# Photomodule.net
KiCad netlist of a schematic drawn in Altium Designer
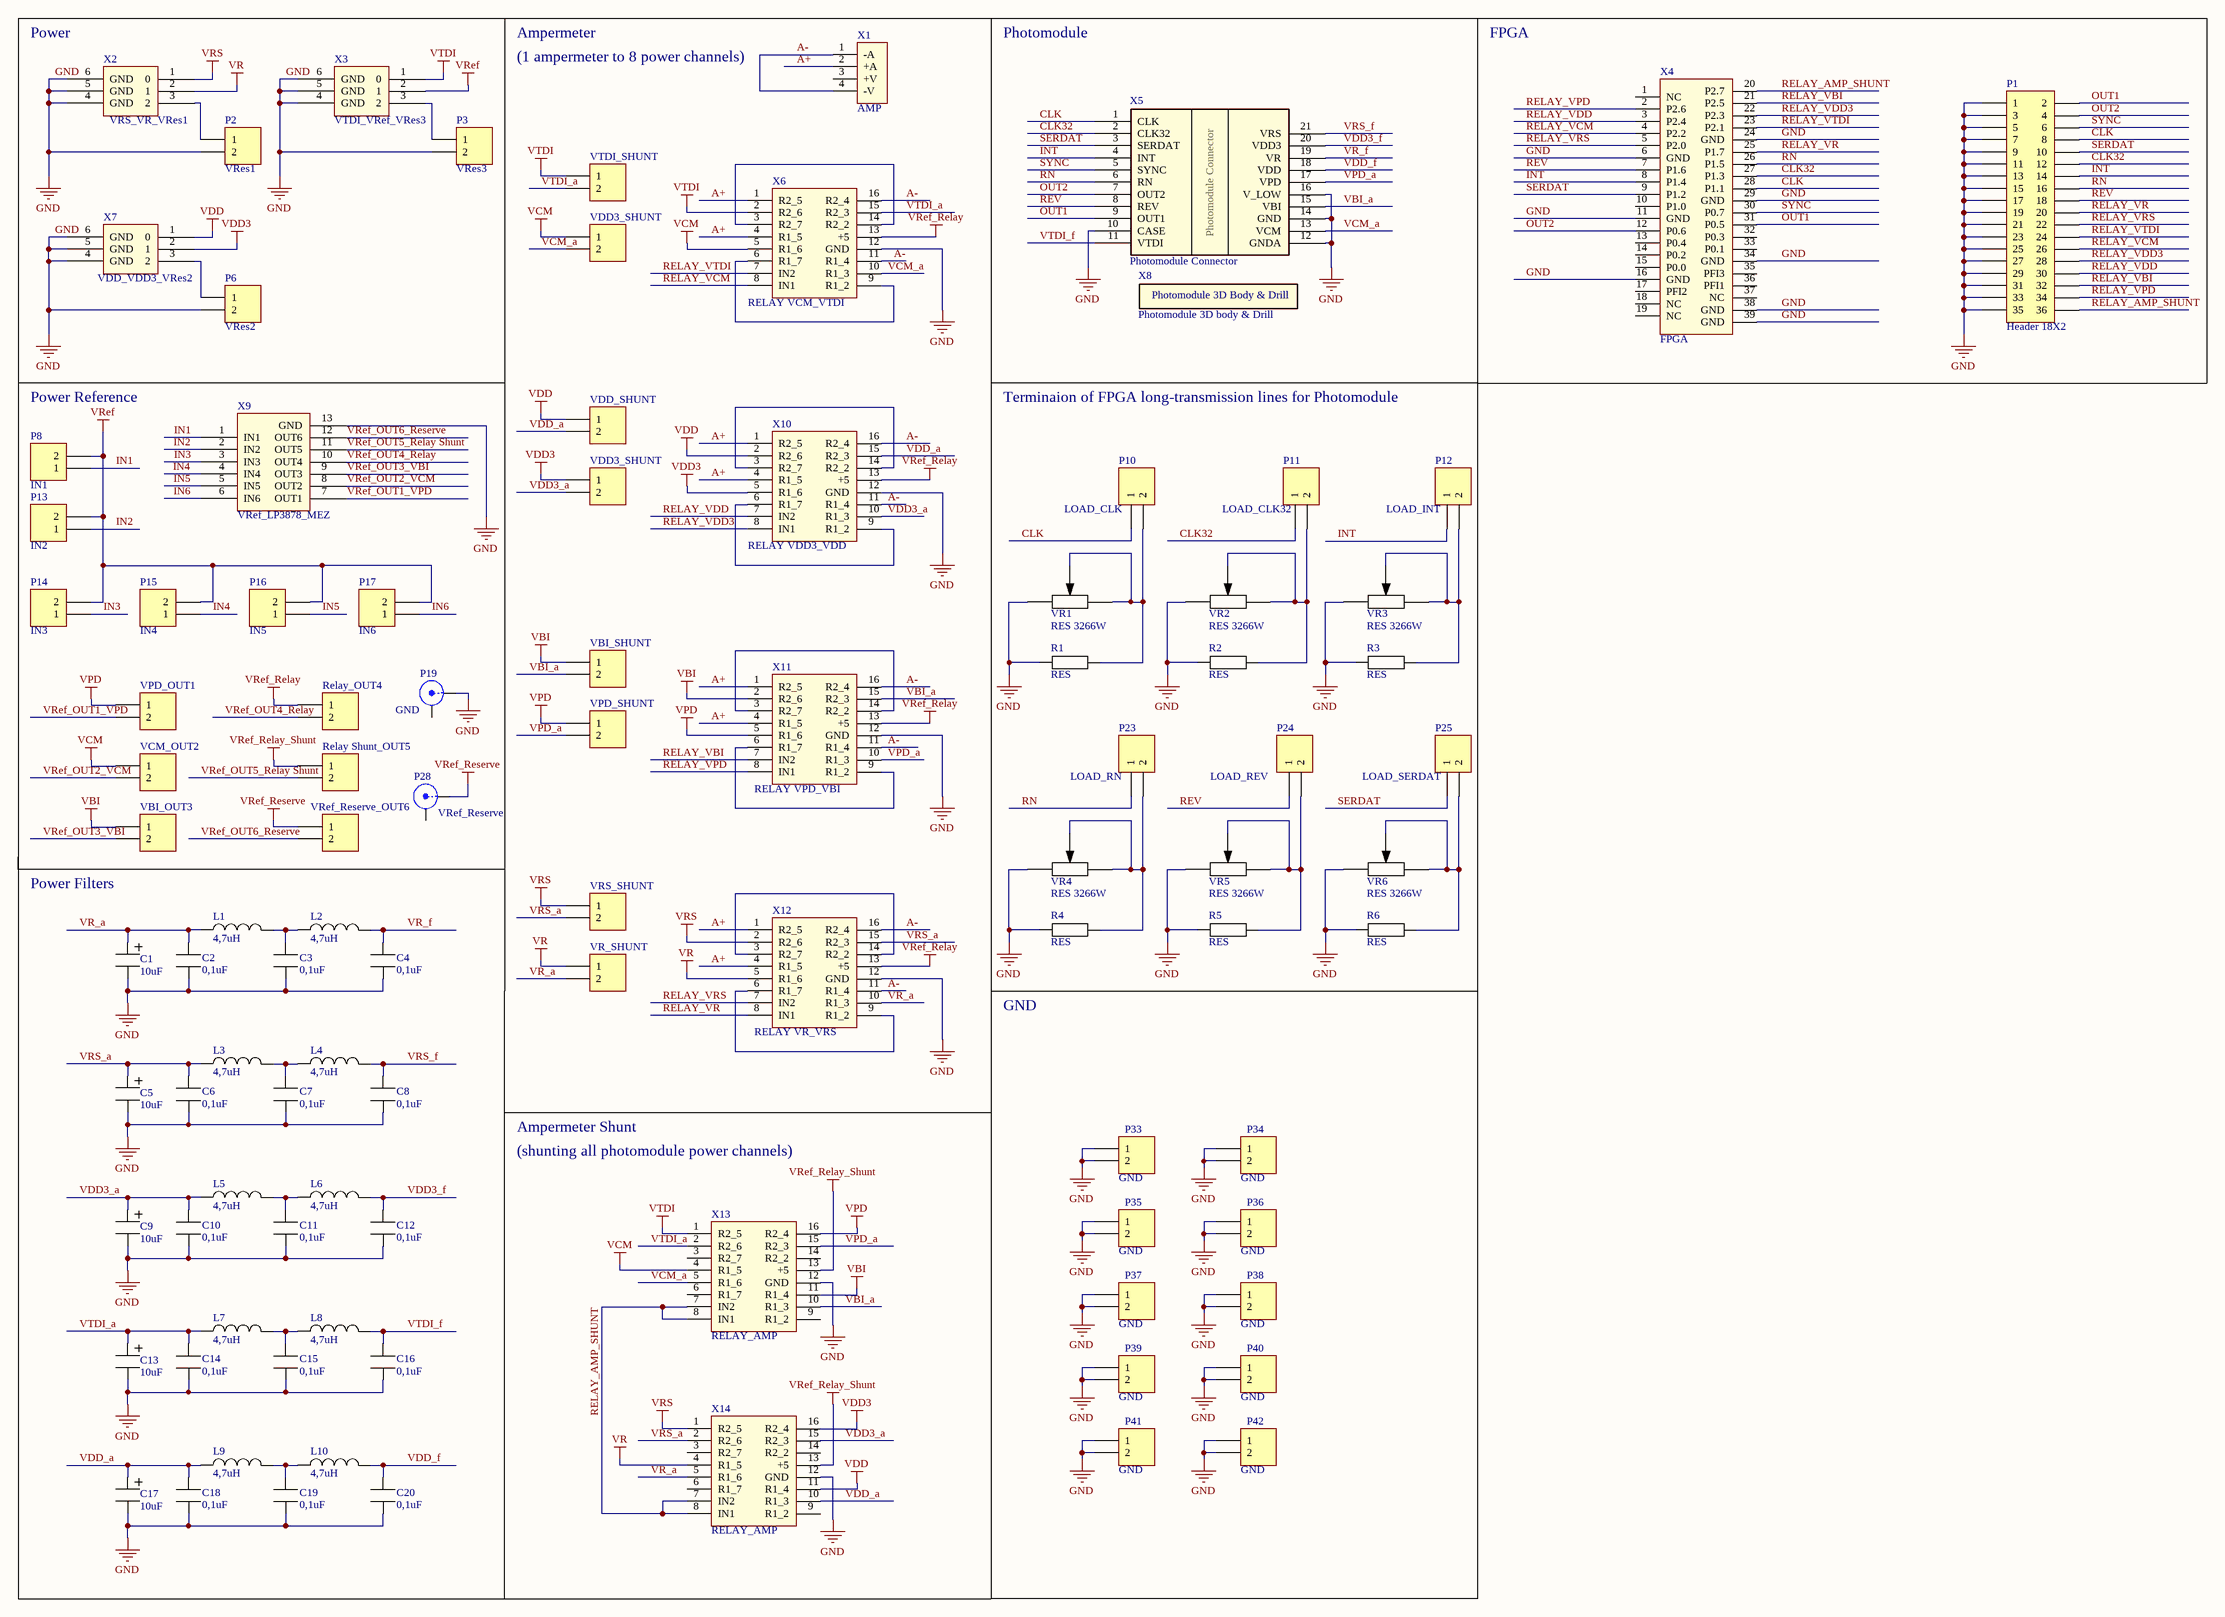
[diagram p0: Photomodule.SchDoc]

(export (version "E")
  (design (tool "Eeschema 10.0.6"))
  (components
    (comp (ref "C1")
      (value "10uF")
      (footprint "aab_Passive:CAP_TANT_TypeC")
      (libsource (lib "aab_Schlib") (part "CAP_Tantalum"))
    )
    (comp (ref "C2")
      (value "0,1uF")
      (footprint "aab_Passive:CAP_0603")
      (libsource (lib "aab_Schlib") (part "CAP"))
    )
    (comp (ref "C3")
      (value "0,1uF")
      (footprint "aab_Passive:CAP_0603")
      (libsource (lib "aab_Schlib") (part "CAP"))
    )
    (comp (ref "C4")
      (value "0,1uF")
      (footprint "aab_Passive:CAP_0603")
      (libsource (lib "aab_Schlib") (part "CAP"))
    )
    (comp (ref "C5")
      (value "10uF")
      (footprint "aab_Passive:CAP_TANT_TypeC")
      (libsource (lib "aab_Schlib") (part "CAP_Tantalum"))
    )
    (comp (ref "C6")
      (value "0,1uF")
      (footprint "aab_Passive:CAP_0603")
      (libsource (lib "aab_Schlib") (part "CAP"))
    )
    (comp (ref "C7")
      (value "0,1uF")
      (footprint "aab_Passive:CAP_0603")
      (libsource (lib "aab_Schlib") (part "CAP"))
    )
    (comp (ref "C8")
      (value "0,1uF")
      (footprint "aab_Passive:CAP_0603")
      (libsource (lib "aab_Schlib") (part "CAP"))
    )
    (comp (ref "C9")
      (value "10uF")
      (footprint "aab_Passive:CAP_TANT_TypeC")
      (libsource (lib "aab_Schlib") (part "CAP_Tantalum"))
    )
    (comp (ref "C10")
      (value "0,1uF")
      (footprint "aab_Passive:CAP_0603")
      (libsource (lib "aab_Schlib") (part "CAP"))
    )
    (comp (ref "C11")
      (value "0,1uF")
      (footprint "aab_Passive:CAP_0603")
      (libsource (lib "aab_Schlib") (part "CAP"))
    )
    (comp (ref "C12")
      (value "0,1uF")
      (footprint "aab_Passive:CAP_0603")
      (libsource (lib "aab_Schlib") (part "CAP"))
    )
    (comp (ref "C13")
      (value "10uF")
      (footprint "aab_Passive:CAP_TANT_TypeC")
      (libsource (lib "aab_Schlib") (part "CAP_Tantalum"))
    )
    (comp (ref "C14")
      (value "0,1uF")
      (footprint "aab_Passive:CAP_0603")
      (libsource (lib "aab_Schlib") (part "CAP"))
    )
    (comp (ref "C15")
      (value "0,1uF")
      (footprint "aab_Passive:CAP_0603")
      (libsource (lib "aab_Schlib") (part "CAP"))
    )
    (comp (ref "C16")
      (value "0,1uF")
      (footprint "aab_Passive:CAP_0603")
      (libsource (lib "aab_Schlib") (part "CAP"))
    )
    (comp (ref "C17")
      (value "10uF")
      (footprint "aab_Passive:CAP_TANT_TypeC")
      (libsource (lib "aab_Schlib") (part "CAP_Tantalum"))
    )
    (comp (ref "C18")
      (value "0,1uF")
      (footprint "aab_Passive:CAP_0603")
      (libsource (lib "aab_Schlib") (part "CAP"))
    )
    (comp (ref "C19")
      (value "0,1uF")
      (footprint "aab_Passive:CAP_0603")
      (libsource (lib "aab_Schlib") (part "CAP"))
    )
    (comp (ref "C20")
      (value "0,1uF")
      (footprint "aab_Passive:CAP_0603")
      (libsource (lib "aab_Schlib") (part "CAP"))
    )
    (comp (ref "L1")
      (value "4,7uH")
      (footprint "aab_Passive:IND_2520")
      (libsource (lib "aab_Schlib") (part "IND"))
    )
    (comp (ref "L2")
      (value "4,7uH")
      (footprint "aab_Passive:IND_2520")
      (libsource (lib "aab_Schlib") (part "IND"))
    )
    (comp (ref "L3")
      (value "4,7uH")
      (footprint "aab_Passive:IND_2520")
      (libsource (lib "aab_Schlib") (part "IND"))
    )
    (comp (ref "L4")
      (value "4,7uH")
      (footprint "aab_Passive:IND_2520")
      (libsource (lib "aab_Schlib") (part "IND"))
    )
    (comp (ref "L5")
      (value "4,7uH")
      (footprint "aab_Passive:IND_2520")
      (libsource (lib "aab_Schlib") (part "IND"))
    )
    (comp (ref "L6")
      (value "4,7uH")
      (footprint "aab_Passive:IND_2520")
      (libsource (lib "aab_Schlib") (part "IND"))
    )
    (comp (ref "L7")
      (value "4,7uH")
      (footprint "aab_Passive:IND_2520")
      (libsource (lib "aab_Schlib") (part "IND"))
    )
    (comp (ref "L8")
      (value "4,7uH")
      (footprint "aab_Passive:IND_2520")
      (libsource (lib "aab_Schlib") (part "IND"))
    )
    (comp (ref "L9")
      (value "4,7uH")
      (footprint "aab_Passive:IND_2520")
      (libsource (lib "aab_Schlib") (part "IND"))
    )
    (comp (ref "L10")
      (value "4,7uH")
      (footprint "aab_Passive:IND_2520")
      (libsource (lib "aab_Schlib") (part "IND"))
    )
    (comp (ref "P1")
      (value "Header 18X2")
      (footprint "HDR2X18")
      (description "Header, 18-Pin, Dual row")
      (fields (field (name "PUBLISHER") "Altium Limited"))
      (libsource (lib "Miscellaneous Connectors") (part "Header 18X2"))
    )
    (comp (ref "P2")
      (value "VRes1")
      (footprint "HDR1X2")
      (description "Header, 2-Pin")
      (fields (field (name "PUBLISHER") "Altium Limited"))
      (libsource (lib "Miscellaneous Connectors") (part "Header 2"))
    )
    (comp (ref "P3")
      (value "VRes3")
      (footprint "HDR1X2")
      (description "Header, 2-Pin")
      (fields (field (name "PUBLISHER") "Altium Limited"))
      (libsource (lib "Miscellaneous Connectors") (part "Header 2"))
    )
    (comp (ref "P4")
      (value "VTDI_SHUNT")
      (footprint "HDR1X2")
      (description "Header, 2-Pin")
      (fields (field (name "PUBLISHER") "Altium Limited"))
      (libsource (lib "Miscellaneous Connectors") (part "Header 2"))
    )
    (comp (ref "P5")
      (value "VDD3_SHUNT")
      (footprint "HDR1X2")
      (description "Header, 2-Pin")
      (fields (field (name "PUBLISHER") "Altium Limited"))
      (libsource (lib "Miscellaneous Connectors") (part "Header 2"))
    )
    (comp (ref "P6")
      (value "VRes2")
      (footprint "HDR1X2")
      (description "Header, 2-Pin")
      (fields (field (name "PUBLISHER") "Altium Limited"))
      (libsource (lib "Miscellaneous Connectors") (part "Header 2"))
    )
    (comp (ref "P7")
      (value "VDD_SHUNT")
      (footprint "HDR1X2")
      (description "Header, 2-Pin")
      (fields (field (name "PUBLISHER") "Altium Limited"))
      (libsource (lib "Miscellaneous Connectors") (part "Header 2"))
    )
    (comp (ref "P8")
      (value "IN1")
      (footprint "HDR1X2")
      (description "Header, 2-Pin")
      (fields (field (name "PUBLISHER") "Altium Limited"))
      (libsource (lib "") (part "Header 2_1"))
    )
    (comp (ref "P9")
      (value "VDD3_SHUNT")
      (footprint "HDR1X2")
      (description "Header, 2-Pin")
      (fields (field (name "PUBLISHER") "Altium Limited"))
      (libsource (lib "Miscellaneous Connectors") (part "Header 2"))
    )
    (comp (ref "P10")
      (value "LOAD_CLK")
      (footprint "HDR1X2")
      (description "Header, 2-Pin")
      (fields (field (name "PUBLISHER") "Altium Limited"))
      (libsource (lib "") (part "Header 2_2"))
    )
    (comp (ref "P11")
      (value "LOAD_CLK32")
      (footprint "HDR1X2")
      (description "Header, 2-Pin")
      (fields (field (name "PUBLISHER") "Altium Limited"))
      (libsource (lib "") (part "Header 2_2"))
    )
    (comp (ref "P12")
      (value "LOAD_INT")
      (footprint "HDR1X2")
      (description "Header, 2-Pin")
      (fields (field (name "PUBLISHER") "Altium Limited"))
      (libsource (lib "") (part "Header 2_2"))
    )
    (comp (ref "P13")
      (value "IN2")
      (footprint "HDR1X2")
      (description "Header, 2-Pin")
      (fields (field (name "PUBLISHER") "Altium Limited"))
      (libsource (lib "") (part "Header 2_1"))
    )
    (comp (ref "P14")
      (value "IN3")
      (footprint "HDR1X2")
      (description "Header, 2-Pin")
      (fields (field (name "PUBLISHER") "Altium Limited"))
      (libsource (lib "") (part "Header 2_1"))
    )
    (comp (ref "P15")
      (value "IN4")
      (footprint "HDR1X2")
      (description "Header, 2-Pin")
      (fields (field (name "PUBLISHER") "Altium Limited"))
      (libsource (lib "") (part "Header 2_1"))
    )
    (comp (ref "P16")
      (value "IN5")
      (footprint "HDR1X2")
      (description "Header, 2-Pin")
      (fields (field (name "PUBLISHER") "Altium Limited"))
      (libsource (lib "") (part "Header 2_1"))
    )
    (comp (ref "P17")
      (value "IN6")
      (footprint "HDR1X2")
      (description "Header, 2-Pin")
      (fields (field (name "PUBLISHER") "Altium Limited"))
      (libsource (lib "") (part "Header 2_1"))
    )
    (comp (ref "P18")
      (value "VBI_SHUNT")
      (footprint "HDR1X2")
      (description "Header, 2-Pin")
      (fields (field (name "PUBLISHER") "Altium Limited"))
      (libsource (lib "Miscellaneous Connectors") (part "Header 2"))
    )
    (comp (ref "P19")
      (value "GND")
      (footprint "BNC_RA CON")
      (description "BNC Elbow Connector")
      (fields (field (name "PUBLISHER") "Altium Limited"))
      (libsource (lib "Miscellaneous Connectors") (part "BNC"))
    )
    (comp (ref "P20")
      (value "VPD_OUT1")
      (footprint "HDR1X2")
      (description "Header, 2-Pin")
      (fields (field (name "PUBLISHER") "Altium Limited"))
      (libsource (lib "Miscellaneous Connectors") (part "Header 2"))
    )
    (comp (ref "P21")
      (value "Relay_OUT4")
      (footprint "HDR1X2")
      (description "Header, 2-Pin")
      (fields (field (name "PUBLISHER") "Altium Limited"))
      (libsource (lib "Miscellaneous Connectors") (part "Header 2"))
    )
    (comp (ref "P22")
      (value "VPD_SHUNT")
      (footprint "HDR1X2")
      (description "Header, 2-Pin")
      (fields (field (name "PUBLISHER") "Altium Limited"))
      (libsource (lib "Miscellaneous Connectors") (part "Header 2"))
    )
    (comp (ref "P23")
      (value "LOAD_RN")
      (footprint "HDR1X2")
      (description "Header, 2-Pin")
      (fields (field (name "PUBLISHER") "Altium Limited"))
      (libsource (lib "") (part "Header 2_2"))
    )
    (comp (ref "P24")
      (value "LOAD_REV")
      (footprint "HDR1X2")
      (description "Header, 2-Pin")
      (fields (field (name "PUBLISHER") "Altium Limited"))
      (libsource (lib "") (part "Header 2_2"))
    )
    (comp (ref "P25")
      (value "LOAD_SERDAT")
      (footprint "HDR1X2")
      (description "Header, 2-Pin")
      (fields (field (name "PUBLISHER") "Altium Limited"))
      (libsource (lib "") (part "Header 2_2"))
    )
    (comp (ref "P26")
      (value "VCM_OUT2")
      (footprint "HDR1X2")
      (description "Header, 2-Pin")
      (fields (field (name "PUBLISHER") "Altium Limited"))
      (libsource (lib "Miscellaneous Connectors") (part "Header 2"))
    )
    (comp (ref "P27")
      (value "Relay Shunt_OUT5")
      (footprint "HDR1X2")
      (description "Header, 2-Pin")
      (fields (field (name "PUBLISHER") "Altium Limited"))
      (libsource (lib "Miscellaneous Connectors") (part "Header 2"))
    )
    (comp (ref "P28")
      (value "VRef_Reserve")
      (footprint "BNC_RA CON")
      (description "BNC Elbow Connector")
      (fields (field (name "PUBLISHER") "Altium Limited"))
      (libsource (lib "Miscellaneous Connectors") (part "BNC"))
    )
    (comp (ref "P29")
      (value "VBI_OUT3")
      (footprint "HDR1X2")
      (description "Header, 2-Pin")
      (fields (field (name "PUBLISHER") "Altium Limited"))
      (libsource (lib "Miscellaneous Connectors") (part "Header 2"))
    )
    (comp (ref "P30")
      (value "VRef_Reserve_OUT6")
      (footprint "HDR1X2")
      (description "Header, 2-Pin")
      (fields (field (name "PUBLISHER") "Altium Limited"))
      (libsource (lib "Miscellaneous Connectors") (part "Header 2"))
    )
    (comp (ref "P31")
      (value "VRS_SHUNT")
      (footprint "HDR1X2")
      (description "Header, 2-Pin")
      (fields (field (name "PUBLISHER") "Altium Limited"))
      (libsource (lib "Miscellaneous Connectors") (part "Header 2"))
    )
    (comp (ref "P32")
      (value "VR_SHUNT")
      (footprint "HDR1X2")
      (description "Header, 2-Pin")
      (fields (field (name "PUBLISHER") "Altium Limited"))
      (libsource (lib "Miscellaneous Connectors") (part "Header 2"))
    )
    (comp (ref "P33")
      (value "GND")
      (footprint "HDR1X2")
      (description "Header, 2-Pin")
      (fields (field (name "PUBLISHER") "Altium Limited"))
      (libsource (lib "Miscellaneous Connectors") (part "Header 2"))
    )
    (comp (ref "P34")
      (value "GND")
      (footprint "HDR1X2")
      (description "Header, 2-Pin")
      (fields (field (name "PUBLISHER") "Altium Limited"))
      (libsource (lib "Miscellaneous Connectors") (part "Header 2"))
    )
    (comp (ref "P35")
      (value "GND")
      (footprint "HDR1X2")
      (description "Header, 2-Pin")
      (fields (field (name "PUBLISHER") "Altium Limited"))
      (libsource (lib "Miscellaneous Connectors") (part "Header 2"))
    )
    (comp (ref "P36")
      (value "GND")
      (footprint "HDR1X2")
      (description "Header, 2-Pin")
      (fields (field (name "PUBLISHER") "Altium Limited"))
      (libsource (lib "Miscellaneous Connectors") (part "Header 2"))
    )
    (comp (ref "P37")
      (value "GND")
      (footprint "HDR1X2")
      (description "Header, 2-Pin")
      (fields (field (name "PUBLISHER") "Altium Limited"))
      (libsource (lib "Miscellaneous Connectors") (part "Header 2"))
    )
    (comp (ref "P38")
      (value "GND")
      (footprint "HDR1X2")
      (description "Header, 2-Pin")
      (fields (field (name "PUBLISHER") "Altium Limited"))
      (libsource (lib "Miscellaneous Connectors") (part "Header 2"))
    )
    (comp (ref "P39")
      (value "GND")
      (footprint "HDR1X2")
      (description "Header, 2-Pin")
      (fields (field (name "PUBLISHER") "Altium Limited"))
      (libsource (lib "Miscellaneous Connectors") (part "Header 2"))
    )
    (comp (ref "P40")
      (value "GND")
      (footprint "HDR1X2")
      (description "Header, 2-Pin")
      (fields (field (name "PUBLISHER") "Altium Limited"))
      (libsource (lib "Miscellaneous Connectors") (part "Header 2"))
    )
    (comp (ref "P41")
      (value "GND")
      (footprint "HDR1X2")
      (description "Header, 2-Pin")
      (fields (field (name "PUBLISHER") "Altium Limited"))
      (libsource (lib "Miscellaneous Connectors") (part "Header 2"))
    )
    (comp (ref "P42")
      (value "GND")
      (footprint "HDR1X2")
      (description "Header, 2-Pin")
      (fields (field (name "PUBLISHER") "Altium Limited"))
      (libsource (lib "Miscellaneous Connectors") (part "Header 2"))
    )
    (comp (ref "R1")
      (value "RES")
      (footprint "aab_Passive:RES_0805")
      (libsource (lib "aab_Schlib") (part "RES"))
    )
    (comp (ref "R2")
      (value "RES")
      (footprint "aab_Passive:RES_0805")
      (libsource (lib "aab_Schlib") (part "RES"))
    )
    (comp (ref "R3")
      (value "RES")
      (footprint "aab_Passive:RES_0805")
      (libsource (lib "aab_Schlib") (part "RES"))
    )
    (comp (ref "R4")
      (value "RES")
      (footprint "aab_Passive:RES_0805")
      (libsource (lib "aab_Schlib") (part "RES"))
    )
    (comp (ref "R5")
      (value "RES")
      (footprint "aab_Passive:RES_0805")
      (libsource (lib "aab_Schlib") (part "RES"))
    )
    (comp (ref "R6")
      (value "RES")
      (footprint "aab_Passive:RES_0805")
      (libsource (lib "aab_Schlib") (part "RES"))
    )
    (comp (ref "VR1")
      (value "RES 3266W")
      (footprint "aab_Passive:RES 3266W")
      (libsource (lib "aab_Schlib") (part "RES 3266W"))
    )
    (comp (ref "VR2")
      (value "RES 3266W")
      (footprint "aab_Passive:RES 3266W")
      (libsource (lib "aab_Schlib") (part "RES 3266W"))
    )
    (comp (ref "VR3")
      (value "RES 3266W")
      (footprint "aab_Passive:RES 3266W")
      (libsource (lib "aab_Schlib") (part "RES 3266W"))
    )
    (comp (ref "VR4")
      (value "RES 3266W")
      (footprint "aab_Passive:RES 3266W")
      (libsource (lib "aab_Schlib") (part "RES 3266W"))
    )
    (comp (ref "VR5")
      (value "RES 3266W")
      (footprint "aab_Passive:RES 3266W")
      (libsource (lib "aab_Schlib") (part "RES 3266W"))
    )
    (comp (ref "VR6")
      (value "RES 3266W")
      (footprint "aab_Passive:RES 3266W")
      (libsource (lib "aab_Schlib") (part "RES 3266W"))
    )
    (comp (ref "X1")
      (value "AMP")
      (footprint "AMP_VOLTMETR")
      (libsource (lib "msp_SchLib") (part "AMP_VOLTMETR"))
    )
    (comp (ref "X2")
      (value "VRS_VR_VRes1")
      (footprint "vpl_Passive_NEW:POWER")
      (libsource (lib "vpl_Schlib_NEW") (part "POWER"))
    )
    (comp (ref "X3")
      (value "VTDI_VRef_VRes3")
      (footprint "vpl_Passive_NEW:POWER")
      (libsource (lib "vpl_Schlib_NEW") (part "POWER"))
    )
    (comp (ref "X4")
      (value "FPGA")
      (footprint "CHEAP_CONN_FEMALE")
      (libsource (lib "vpl_Schlib") (part "CHEAP_CON_37_FEMALE"))
    )
    (comp (ref "X5")
      (value "Photomodule Connector")
      (footprint "aab_Active:Photomodule_Electric")
      (libsource (lib "aab_Schlib") (part "Photomodule Connector"))
    )
    (comp (ref "X6")
      (value "RELAY VCM_VTDI")
      (footprint "RELAY_MODULE")
      (libsource (lib "vpl_Schlib") (part "MEZON_RELAY"))
    )
    (comp (ref "X7")
      (value "VDD_VDD3_VRes2")
      (footprint "vpl_Passive_NEW:POWER")
      (libsource (lib "vpl_Schlib_NEW") (part "POWER"))
    )
    (comp (ref "X8")
      (value "Photomodule 3D body & Drill")
      (footprint "aab_Passive:Photomodule_3D Body & Drill")
      (libsource (lib "aab_Schlib") (part "Phoromodule 3D body & Drill"))
    )
    (comp (ref "X9")
      (value "VRef_LP3878_MEZ")
      (footprint "aab_Active:VRef_LP3878_MEZ")
      (libsource (lib "aab_Schlib") (part "VRef_LP3878_MEZ"))
    )
    (comp (ref "X10")
      (value "RELAY VDD3_VDD")
      (footprint "RELAY_MODULE")
      (libsource (lib "vpl_Schlib") (part "MEZON_RELAY"))
    )
    (comp (ref "X11")
      (value "RELAY VPD_VBI")
      (footprint "RELAY_MODULE")
      (libsource (lib "vpl_Schlib") (part "MEZON_RELAY"))
    )
    (comp (ref "X12")
      (value "RELAY VR_VRS")
      (footprint "RELAY_MODULE")
      (libsource (lib "vpl_Schlib") (part "MEZON_RELAY"))
    )
    (comp (ref "X13")
      (value "RELAY_AMP")
      (footprint "RELAY_MODULE")
      (libsource (lib "vpl_Schlib") (part "MEZON_RELAY"))
    )
    (comp (ref "X14")
      (value "RELAY_AMP")
      (footprint "RELAY_MODULE")
      (libsource (lib "vpl_Schlib") (part "MEZON_RELAY"))
    )
  )
  (nets
    (net (code "1") (name "/A+") (class "Default")
      (node (ref "X1") (pin "2") (pinfunction "+A_2") (pintype "passive"))
      (node (ref "X10") (pin "1") (pinfunction "R2_5_1") (pintype "passive"))
      (node (ref "X10") (pin "4") (pinfunction "R1_5_4") (pintype "passive"))
      (node (ref "X11") (pin "1") (pinfunction "R2_5_1") (pintype "passive"))
      (node (ref "X11") (pin "4") (pinfunction "R1_5_4") (pintype "passive"))
      (node (ref "X12") (pin "1") (pinfunction "R2_5_1") (pintype "passive"))
      (node (ref "X12") (pin "4") (pinfunction "R1_5_4") (pintype "passive"))
      (node (ref "X6") (pin "1") (pinfunction "R2_5_1") (pintype "passive"))
      (node (ref "X6") (pin "4") (pinfunction "R1_5_4") (pintype "passive"))
    )
    (net (code "2") (name "/A-") (class "Default")
      (node (ref "X1") (pin "1") (pinfunction "-A_1") (pintype "passive"))
      (node (ref "X1") (pin "4") (pinfunction "-V_4") (pintype "passive"))
      (node (ref "X10") (pin "11") (pinfunction "R1_4_11") (pintype "passive"))
      (node (ref "X10") (pin "16") (pinfunction "R2_4_16") (pintype "passive"))
      (node (ref "X11") (pin "11") (pinfunction "R1_4_11") (pintype "passive"))
      (node (ref "X11") (pin "16") (pinfunction "R2_4_16") (pintype "passive"))
      (node (ref "X12") (pin "11") (pinfunction "R1_4_11") (pintype "passive"))
      (node (ref "X12") (pin "16") (pinfunction "R2_4_16") (pintype "passive"))
      (node (ref "X6") (pin "11") (pinfunction "R1_4_11") (pintype "passive"))
      (node (ref "X6") (pin "16") (pinfunction "R2_4_16") (pintype "passive"))
    )
    (net (code "3") (name "/CLK") (class "Default")
      (node (ref "P1") (pin "8") (pinfunction "8_8") (pintype "passive"))
      (node (ref "P10") (pin "1") (pinfunction "1_1") (pintype "passive"))
      (node (ref "X4") (pin "28") (pinfunction "P1.1_28") (pintype "passive"))
      (node (ref "X5") (pin "1") (pinfunction "CLK_1") (pintype "passive"))
    )
    (net (code "4") (name "/CLK32") (class "Default")
      (node (ref "P1") (pin "12") (pinfunction "12_12") (pintype "passive"))
      (node (ref "P11") (pin "1") (pinfunction "1_1") (pintype "passive"))
      (node (ref "X4") (pin "27") (pinfunction "P1.3_27") (pintype "passive"))
      (node (ref "X5") (pin "2") (pinfunction "CLK32_2") (pintype "passive"))
    )
    (net (code "5") (name "/IN1") (class "Default")
      (node (ref "P8") (pin "1") (pinfunction "1_1") (pintype "passive"))
      (node (ref "X9") (pin "1") (pinfunction "IN1_1") (pintype "passive"))
    )
    (net (code "6") (name "/IN2") (class "Default")
      (node (ref "P13") (pin "1") (pinfunction "1_1") (pintype "passive"))
      (node (ref "X9") (pin "2") (pinfunction "IN2_2") (pintype "passive"))
    )
    (net (code "7") (name "/IN3") (class "Default")
      (node (ref "P14") (pin "1") (pinfunction "1_1") (pintype "passive"))
      (node (ref "X9") (pin "3") (pinfunction "IN3_3") (pintype "passive"))
    )
    (net (code "8") (name "/IN4") (class "Default")
      (node (ref "P15") (pin "1") (pinfunction "1_1") (pintype "passive"))
      (node (ref "X9") (pin "4") (pinfunction "IN4_4") (pintype "passive"))
    )
    (net (code "9") (name "/IN5") (class "Default")
      (node (ref "P16") (pin "1") (pinfunction "1_1") (pintype "passive"))
      (node (ref "X9") (pin "5") (pinfunction "IN5_5") (pintype "passive"))
    )
    (net (code "10") (name "/IN6") (class "Default")
      (node (ref "P17") (pin "1") (pinfunction "1_1") (pintype "passive"))
      (node (ref "X9") (pin "6") (pinfunction "IN6_6") (pintype "passive"))
    )
    (net (code "11") (name "/INT") (class "Default")
      (node (ref "P1") (pin "14") (pinfunction "14_14") (pintype "passive"))
      (node (ref "P12") (pin "1") (pinfunction "1_1") (pintype "passive"))
      (node (ref "X4") (pin "8") (pinfunction "P1.4_8") (pintype "passive"))
      (node (ref "X5") (pin "4") (pinfunction "INT_4") (pintype "passive"))
    )
    (net (code "12") (name "/OUT1") (class "Default")
      (node (ref "P1") (pin "2") (pinfunction "2_2") (pintype "passive"))
      (node (ref "X4") (pin "31") (pinfunction "P0.5_31") (pintype "passive"))
      (node (ref "X5") (pin "9") (pinfunction "OUT1_9") (pintype "passive"))
    )
    (net (code "13") (name "/OUT2") (class "Default")
      (node (ref "P1") (pin "4") (pinfunction "4_4") (pintype "passive"))
      (node (ref "X4") (pin "12") (pinfunction "P0.6_12") (pintype "passive"))
      (node (ref "X5") (pin "7") (pinfunction "OUT2_7") (pintype "passive"))
    )
    (net (code "14") (name "/RELAY_AMP_SHUNT") (class "Default")
      (node (ref "P1") (pin "36") (pinfunction "36_36") (pintype "passive"))
      (node (ref "X13") (pin "7") (pinfunction "IN2_7") (pintype "passive"))
      (node (ref "X13") (pin "8") (pinfunction "IN1_8") (pintype "passive"))
      (node (ref "X14") (pin "7") (pinfunction "IN2_7") (pintype "passive"))
      (node (ref "X14") (pin "8") (pinfunction "IN1_8") (pintype "passive"))
      (node (ref "X4") (pin "20") (pinfunction "P2.7_20") (pintype "passive"))
    )
    (net (code "15") (name "/RELAY_VBI") (class "Default")
      (node (ref "P1") (pin "32") (pinfunction "32_32") (pintype "passive"))
      (node (ref "X11") (pin "7") (pinfunction "IN2_7") (pintype "passive"))
      (node (ref "X4") (pin "21") (pinfunction "P2.5_21") (pintype "passive"))
    )
    (net (code "16") (name "/RELAY_VCM") (class "Default")
      (node (ref "P1") (pin "26") (pinfunction "26_26") (pintype "passive"))
      (node (ref "X4") (pin "4") (pinfunction "P2.2_4") (pintype "passive"))
      (node (ref "X6") (pin "8") (pinfunction "IN1_8") (pintype "passive"))
    )
    (net (code "17") (name "/RELAY_VDD") (class "Default")
      (node (ref "P1") (pin "30") (pinfunction "30_30") (pintype "passive"))
      (node (ref "X10") (pin "7") (pinfunction "IN2_7") (pintype "passive"))
      (node (ref "X4") (pin "3") (pinfunction "P2.4_3") (pintype "passive"))
    )
    (net (code "18") (name "/RELAY_VDD3") (class "Default")
      (node (ref "P1") (pin "28") (pinfunction "28_28") (pintype "passive"))
      (node (ref "X10") (pin "8") (pinfunction "IN1_8") (pintype "passive"))
      (node (ref "X4") (pin "22") (pinfunction "P2.3_22") (pintype "passive"))
    )
    (net (code "19") (name "/RELAY_VPD") (class "Default")
      (node (ref "P1") (pin "34") (pinfunction "34_34") (pintype "passive"))
      (node (ref "X11") (pin "8") (pinfunction "IN1_8") (pintype "passive"))
      (node (ref "X4") (pin "2") (pinfunction "P2.6_2") (pintype "passive"))
    )
    (net (code "20") (name "/RELAY_VR") (class "Default")
      (node (ref "P1") (pin "20") (pinfunction "20_20") (pintype "passive"))
      (node (ref "X12") (pin "8") (pinfunction "IN1_8") (pintype "passive"))
      (node (ref "X4") (pin "25") (pinfunction "P1.7_25") (pintype "passive"))
    )
    (net (code "21") (name "/RELAY_VRS") (class "Default")
      (node (ref "P1") (pin "22") (pinfunction "22_22") (pintype "passive"))
      (node (ref "X12") (pin "7") (pinfunction "IN2_7") (pintype "passive"))
      (node (ref "X4") (pin "5") (pinfunction "P2.0_5") (pintype "passive"))
    )
    (net (code "22") (name "/RELAY_VTDI") (class "Default")
      (node (ref "P1") (pin "24") (pinfunction "24_24") (pintype "passive"))
      (node (ref "X4") (pin "23") (pinfunction "P2.1_23") (pintype "passive"))
      (node (ref "X6") (pin "7") (pinfunction "IN2_7") (pintype "passive"))
    )
    (net (code "23") (name "/REV") (class "Default")
      (node (ref "P1") (pin "18") (pinfunction "18_18") (pintype "passive"))
      (node (ref "P24") (pin "1") (pinfunction "1_1") (pintype "passive"))
      (node (ref "X4") (pin "7") (pinfunction "P1.6_7") (pintype "passive"))
      (node (ref "X5") (pin "8") (pinfunction "REV_8") (pintype "passive"))
    )
    (net (code "24") (name "/RN") (class "Default")
      (node (ref "P1") (pin "16") (pinfunction "16_16") (pintype "passive"))
      (node (ref "P23") (pin "1") (pinfunction "1_1") (pintype "passive"))
      (node (ref "X4") (pin "26") (pinfunction "P1.5_26") (pintype "passive"))
      (node (ref "X5") (pin "6") (pinfunction "RN_6") (pintype "passive"))
    )
    (net (code "25") (name "/SERDAT") (class "Default")
      (node (ref "P1") (pin "10") (pinfunction "10_10") (pintype "passive"))
      (node (ref "P25") (pin "1") (pinfunction "1_1") (pintype "passive"))
      (node (ref "X4") (pin "9") (pinfunction "P1.2_9") (pintype "passive"))
      (node (ref "X5") (pin "3") (pinfunction "SERDAT_3") (pintype "passive"))
    )
    (net (code "26") (name "/SYNC") (class "Default")
      (node (ref "P1") (pin "6") (pinfunction "6_6") (pintype "passive"))
      (node (ref "X4") (pin "30") (pinfunction "P0.7_30") (pintype "passive"))
      (node (ref "X5") (pin "5") (pinfunction "SYNC_5") (pintype "passive"))
    )
    (net (code "27") (name "/VBI_a") (class "Default")
      (node (ref "P18") (pin "2") (pinfunction "2_2") (pintype "passive"))
      (node (ref "X11") (pin "15") (pinfunction "R2_3_15") (pintype "passive"))
      (node (ref "X13") (pin "10") (pinfunction "R1_3_10") (pintype "passive"))
      (node (ref "X5") (pin "15") (pinfunction "VBI_15") (pintype "passive"))
    )
    (net (code "28") (name "/VCM_a") (class "Default")
      (node (ref "P5") (pin "2") (pinfunction "2_2") (pintype "passive"))
      (node (ref "X13") (pin "5") (pinfunction "R1_6_5") (pintype "passive"))
      (node (ref "X5") (pin "13") (pinfunction "VCM_13") (pintype "passive"))
      (node (ref "X6") (pin "10") (pinfunction "R1_3_10") (pintype "passive"))
    )
    (net (code "29") (name "/VDD3_a") (class "Default")
      (node (ref "C10") (pin "2") (pinfunction "2_2") (pintype "passive"))
      (node (ref "C9") (pin "1") (pinfunction "1_1") (pintype "passive"))
      (node (ref "L5") (pin "1") (pinfunction "1_1") (pintype "passive"))
      (node (ref "P9") (pin "2") (pinfunction "2_2") (pintype "passive"))
      (node (ref "X10") (pin "10") (pinfunction "R1_3_10") (pintype "passive"))
      (node (ref "X14") (pin "15") (pinfunction "R2_3_15") (pintype "passive"))
    )
    (net (code "30") (name "/VDD3_f") (class "Default")
      (node (ref "C12") (pin "2") (pinfunction "2_2") (pintype "passive"))
      (node (ref "L6") (pin "2") (pinfunction "2_2") (pintype "passive"))
      (node (ref "X5") (pin "20") (pinfunction "VDD3_20") (pintype "passive"))
    )
    (net (code "31") (name "/VDD_a") (class "Default")
      (node (ref "C17") (pin "1") (pinfunction "1_1") (pintype "passive"))
      (node (ref "C18") (pin "2") (pinfunction "2_2") (pintype "passive"))
      (node (ref "L9") (pin "1") (pinfunction "1_1") (pintype "passive"))
      (node (ref "P7") (pin "2") (pinfunction "2_2") (pintype "passive"))
      (node (ref "X10") (pin "15") (pinfunction "R2_3_15") (pintype "passive"))
      (node (ref "X14") (pin "10") (pinfunction "R1_3_10") (pintype "passive"))
    )
    (net (code "32") (name "/VDD_f") (class "Default")
      (node (ref "C20") (pin "2") (pinfunction "2_2") (pintype "passive"))
      (node (ref "L10") (pin "2") (pinfunction "2_2") (pintype "passive"))
      (node (ref "X5") (pin "18") (pinfunction "VDD_18") (pintype "passive"))
    )
    (net (code "33") (name "/VPD_a") (class "Default")
      (node (ref "P22") (pin "2") (pinfunction "2_2") (pintype "passive"))
      (node (ref "X11") (pin "10") (pinfunction "R1_3_10") (pintype "passive"))
      (node (ref "X13") (pin "15") (pinfunction "R2_3_15") (pintype "passive"))
      (node (ref "X5") (pin "17") (pinfunction "VPD_17") (pintype "passive"))
    )
    (net (code "34") (name "/VRS_a") (class "Default")
      (node (ref "C5") (pin "1") (pinfunction "1_1") (pintype "passive"))
      (node (ref "C6") (pin "2") (pinfunction "2_2") (pintype "passive"))
      (node (ref "L3") (pin "1") (pinfunction "1_1") (pintype "passive"))
      (node (ref "P31") (pin "2") (pinfunction "2_2") (pintype "passive"))
      (node (ref "X12") (pin "15") (pinfunction "R2_3_15") (pintype "passive"))
      (node (ref "X14") (pin "2") (pinfunction "R2_6_2") (pintype "passive"))
    )
    (net (code "35") (name "/VRS_f") (class "Default")
      (node (ref "C8") (pin "2") (pinfunction "2_2") (pintype "passive"))
      (node (ref "L4") (pin "2") (pinfunction "2_2") (pintype "passive"))
      (node (ref "X5") (pin "21") (pinfunction "VRS_21") (pintype "passive"))
    )
    (net (code "36") (name "/VR_a") (class "Default")
      (node (ref "C1") (pin "1") (pinfunction "1_1") (pintype "passive"))
      (node (ref "C2") (pin "2") (pinfunction "2_2") (pintype "passive"))
      (node (ref "L1") (pin "1") (pinfunction "1_1") (pintype "passive"))
      (node (ref "P32") (pin "2") (pinfunction "2_2") (pintype "passive"))
      (node (ref "X12") (pin "10") (pinfunction "R1_3_10") (pintype "passive"))
      (node (ref "X14") (pin "5") (pinfunction "R1_6_5") (pintype "passive"))
    )
    (net (code "37") (name "/VR_f") (class "Default")
      (node (ref "C4") (pin "2") (pinfunction "2_2") (pintype "passive"))
      (node (ref "L2") (pin "2") (pinfunction "2_2") (pintype "passive"))
      (node (ref "X5") (pin "19") (pinfunction "VR_19") (pintype "passive"))
    )
    (net (code "38") (name "/VRef_OUT1_VPD") (class "Default")
      (node (ref "P20") (pin "2") (pinfunction "2_2") (pintype "passive"))
      (node (ref "X9") (pin "7") (pinfunction "OUT1_7") (pintype "passive"))
    )
    (net (code "39") (name "/VRef_OUT2_VCM") (class "Default")
      (node (ref "P26") (pin "2") (pinfunction "2_2") (pintype "passive"))
      (node (ref "X9") (pin "8") (pinfunction "OUT2_8") (pintype "passive"))
    )
    (net (code "40") (name "/VRef_OUT3_VBI") (class "Default")
      (node (ref "P29") (pin "2") (pinfunction "2_2") (pintype "passive"))
      (node (ref "X9") (pin "9") (pinfunction "OUT3_9") (pintype "passive"))
    )
    (net (code "41") (name "/VRef_OUT4_Relay") (class "Default")
      (node (ref "P21") (pin "2") (pinfunction "2_2") (pintype "passive"))
      (node (ref "X9") (pin "10") (pinfunction "OUT4_10") (pintype "passive"))
    )
    (net (code "42") (name "/VRef_OUT5_Relay Shunt") (class "Default")
      (node (ref "P27") (pin "2") (pinfunction "2_2") (pintype "passive"))
      (node (ref "X9") (pin "11") (pinfunction "OUT5_11") (pintype "passive"))
    )
    (net (code "43") (name "/VRef_OUT6_Reserve") (class "Default")
      (node (ref "P30") (pin "2") (pinfunction "2_2") (pintype "passive"))
      (node (ref "X9") (pin "12") (pinfunction "OUT6_12") (pintype "passive"))
    )
    (net (code "44") (name "/VTDI_a") (class "Default")
      (node (ref "C13") (pin "1") (pinfunction "1_1") (pintype "passive"))
      (node (ref "C14") (pin "2") (pinfunction "2_2") (pintype "passive"))
      (node (ref "L7") (pin "1") (pinfunction "1_1") (pintype "passive"))
      (node (ref "P4") (pin "2") (pinfunction "2_2") (pintype "passive"))
      (node (ref "X13") (pin "2") (pinfunction "R2_6_2") (pintype "passive"))
      (node (ref "X6") (pin "15") (pinfunction "R2_3_15") (pintype "passive"))
    )
    (net (code "45") (name "/VTDI_f") (class "Default")
      (node (ref "C16") (pin "2") (pinfunction "2_2") (pintype "passive"))
      (node (ref "L8") (pin "2") (pinfunction "2_2") (pintype "passive"))
      (node (ref "X5") (pin "11") (pinfunction "VTDI_11") (pintype "passive"))
    )
    (net (code "46") (name "GND") (class "Default")
      (node (ref "C1") (pin "2") (pinfunction "2_2") (pintype "passive"))
      (node (ref "C10") (pin "1") (pinfunction "1_1") (pintype "passive"))
      (node (ref "C11") (pin "1") (pinfunction "1_1") (pintype "passive"))
      (node (ref "C12") (pin "1") (pinfunction "1_1") (pintype "passive"))
      (node (ref "C13") (pin "2") (pinfunction "2_2") (pintype "passive"))
      (node (ref "C14") (pin "1") (pinfunction "1_1") (pintype "passive"))
      (node (ref "C15") (pin "1") (pinfunction "1_1") (pintype "passive"))
      (node (ref "C16") (pin "1") (pinfunction "1_1") (pintype "passive"))
      (node (ref "C17") (pin "2") (pinfunction "2_2") (pintype "passive"))
      (node (ref "C18") (pin "1") (pinfunction "1_1") (pintype "passive"))
      (node (ref "C19") (pin "1") (pinfunction "1_1") (pintype "passive"))
      (node (ref "C2") (pin "1") (pinfunction "1_1") (pintype "passive"))
      (node (ref "C20") (pin "1") (pinfunction "1_1") (pintype "passive"))
      (node (ref "C3") (pin "1") (pinfunction "1_1") (pintype "passive"))
      (node (ref "C4") (pin "1") (pinfunction "1_1") (pintype "passive"))
      (node (ref "C5") (pin "2") (pinfunction "2_2") (pintype "passive"))
      (node (ref "C6") (pin "1") (pinfunction "1_1") (pintype "passive"))
      (node (ref "C7") (pin "1") (pinfunction "1_1") (pintype "passive"))
      (node (ref "C8") (pin "1") (pinfunction "1_1") (pintype "passive"))
      (node (ref "C9") (pin "2") (pinfunction "2_2") (pintype "passive"))
      (node (ref "P1") (pin "1") (pinfunction "1_1") (pintype "passive"))
      (node (ref "P1") (pin "11") (pinfunction "11_11") (pintype "passive"))
      (node (ref "P1") (pin "13") (pinfunction "13_13") (pintype "passive"))
      (node (ref "P1") (pin "15") (pinfunction "15_15") (pintype "passive"))
      (node (ref "P1") (pin "17") (pinfunction "17_17") (pintype "passive"))
      (node (ref "P1") (pin "19") (pinfunction "19_19") (pintype "passive"))
      (node (ref "P1") (pin "21") (pinfunction "21_21") (pintype "passive"))
      (node (ref "P1") (pin "23") (pinfunction "23_23") (pintype "passive"))
      (node (ref "P1") (pin "25") (pinfunction "25_25") (pintype "passive"))
      (node (ref "P1") (pin "27") (pinfunction "27_27") (pintype "passive"))
      (node (ref "P1") (pin "29") (pinfunction "29_29") (pintype "passive"))
      (node (ref "P1") (pin "3") (pinfunction "3_3") (pintype "passive"))
      (node (ref "P1") (pin "31") (pinfunction "31_31") (pintype "passive"))
      (node (ref "P1") (pin "33") (pinfunction "33_33") (pintype "passive"))
      (node (ref "P1") (pin "35") (pinfunction "35_35") (pintype "passive"))
      (node (ref "P1") (pin "5") (pinfunction "5_5") (pintype "passive"))
      (node (ref "P1") (pin "7") (pinfunction "7_7") (pintype "passive"))
      (node (ref "P1") (pin "9") (pinfunction "9_9") (pintype "passive"))
      (node (ref "P19") (pin "1") (pinfunction "X_1") (pintype "passive"))
      (node (ref "P2") (pin "2") (pinfunction "2_2") (pintype "passive"))
      (node (ref "P3") (pin "2") (pinfunction "2_2") (pintype "passive"))
      (node (ref "P33") (pin "1") (pinfunction "1_1") (pintype "passive"))
      (node (ref "P33") (pin "2") (pinfunction "2_2") (pintype "passive"))
      (node (ref "P34") (pin "1") (pinfunction "1_1") (pintype "passive"))
      (node (ref "P34") (pin "2") (pinfunction "2_2") (pintype "passive"))
      (node (ref "P35") (pin "1") (pinfunction "1_1") (pintype "passive"))
      (node (ref "P35") (pin "2") (pinfunction "2_2") (pintype "passive"))
      (node (ref "P36") (pin "1") (pinfunction "1_1") (pintype "passive"))
      (node (ref "P36") (pin "2") (pinfunction "2_2") (pintype "passive"))
      (node (ref "P37") (pin "1") (pinfunction "1_1") (pintype "passive"))
      (node (ref "P37") (pin "2") (pinfunction "2_2") (pintype "passive"))
      (node (ref "P38") (pin "1") (pinfunction "1_1") (pintype "passive"))
      (node (ref "P38") (pin "2") (pinfunction "2_2") (pintype "passive"))
      (node (ref "P39") (pin "1") (pinfunction "1_1") (pintype "passive"))
      (node (ref "P39") (pin "2") (pinfunction "2_2") (pintype "passive"))
      (node (ref "P40") (pin "1") (pinfunction "1_1") (pintype "passive"))
      (node (ref "P40") (pin "2") (pinfunction "2_2") (pintype "passive"))
      (node (ref "P41") (pin "1") (pinfunction "1_1") (pintype "passive"))
      (node (ref "P41") (pin "2") (pinfunction "2_2") (pintype "passive"))
      (node (ref "P42") (pin "1") (pinfunction "1_1") (pintype "passive"))
      (node (ref "P42") (pin "2") (pinfunction "2_2") (pintype "passive"))
      (node (ref "P6") (pin "2") (pinfunction "2_2") (pintype "passive"))
      (node (ref "R1") (pin "1") (pinfunction "1_1") (pintype "passive"))
      (node (ref "R2") (pin "1") (pinfunction "1_1") (pintype "passive"))
      (node (ref "R3") (pin "1") (pinfunction "1_1") (pintype "passive"))
      (node (ref "R4") (pin "1") (pinfunction "1_1") (pintype "passive"))
      (node (ref "R5") (pin "1") (pinfunction "1_1") (pintype "passive"))
      (node (ref "R6") (pin "1") (pinfunction "1_1") (pintype "passive"))
      (node (ref "VR1") (pin "1") (pinfunction "1_1") (pintype "passive"))
      (node (ref "VR2") (pin "1") (pinfunction "1_1") (pintype "passive"))
      (node (ref "VR3") (pin "1") (pinfunction "1_1") (pintype "passive"))
      (node (ref "VR4") (pin "1") (pinfunction "1_1") (pintype "passive"))
      (node (ref "VR5") (pin "1") (pinfunction "1_1") (pintype "passive"))
      (node (ref "VR6") (pin "1") (pinfunction "1_1") (pintype "passive"))
      (node (ref "X10") (pin "12") (pinfunction "GND_12") (pintype "passive"))
      (node (ref "X11") (pin "12") (pinfunction "GND_12") (pintype "passive"))
      (node (ref "X12") (pin "12") (pinfunction "GND_12") (pintype "passive"))
      (node (ref "X13") (pin "12") (pinfunction "GND_12") (pintype "passive"))
      (node (ref "X14") (pin "12") (pinfunction "GND_12") (pintype "passive"))
      (node (ref "X2") (pin "4") (pinfunction "GND_4") (pintype "passive"))
      (node (ref "X2") (pin "5") (pinfunction "GND_5") (pintype "passive"))
      (node (ref "X2") (pin "6") (pinfunction "GND_6") (pintype "passive"))
      (node (ref "X3") (pin "4") (pinfunction "GND_4") (pintype "passive"))
      (node (ref "X3") (pin "5") (pinfunction "GND_5") (pintype "passive"))
      (node (ref "X3") (pin "6") (pinfunction "GND_6") (pintype "passive"))
      (node (ref "X4") (pin "11") (pinfunction "GND_11") (pintype "passive"))
      (node (ref "X4") (pin "16") (pinfunction "GND_16") (pintype "passive"))
      (node (ref "X4") (pin "24") (pinfunction "GND_24") (pintype "passive"))
      (node (ref "X4") (pin "29") (pinfunction "GND_29") (pintype "passive"))
      (node (ref "X4") (pin "34") (pinfunction "GND_34") (pintype "passive"))
      (node (ref "X4") (pin "38") (pinfunction "GND_38") (pintype "passive"))
      (node (ref "X4") (pin "39") (pinfunction "GND_39") (pintype "passive"))
      (node (ref "X4") (pin "6") (pinfunction "GND_6") (pintype "passive"))
      (node (ref "X5") (pin "10") (pinfunction "CASE_10") (pintype "passive"))
      (node (ref "X5") (pin "12") (pinfunction "GNDA_12") (pintype "passive"))
      (node (ref "X5") (pin "14") (pinfunction "GND_14") (pintype "passive"))
      (node (ref "X5") (pin "16") (pinfunction "V_LOW_16") (pintype "passive"))
      (node (ref "X6") (pin "12") (pinfunction "GND_12") (pintype "passive"))
      (node (ref "X7") (pin "4") (pinfunction "GND_4") (pintype "passive"))
      (node (ref "X7") (pin "5") (pinfunction "GND_5") (pintype "passive"))
      (node (ref "X7") (pin "6") (pinfunction "GND_6") (pintype "passive"))
      (node (ref "X9") (pin "13") (pinfunction "GND_13") (pintype "passive"))
    )
    (net (code "47") (name "Net-(C3-Pad2)") (class "Default")
      (node (ref "C3") (pin "2") (pinfunction "2_2") (pintype "passive"))
      (node (ref "L1") (pin "2") (pinfunction "2_2") (pintype "passive"))
      (node (ref "L2") (pin "1") (pinfunction "1_1") (pintype "passive"))
    )
    (net (code "48") (name "Net-(C7-Pad2)") (class "Default")
      (node (ref "C7") (pin "2") (pinfunction "2_2") (pintype "passive"))
      (node (ref "L3") (pin "2") (pinfunction "2_2") (pintype "passive"))
      (node (ref "L4") (pin "1") (pinfunction "1_1") (pintype "passive"))
    )
    (net (code "49") (name "Net-(C11-Pad2)") (class "Default")
      (node (ref "C11") (pin "2") (pinfunction "2_2") (pintype "passive"))
      (node (ref "L5") (pin "2") (pinfunction "2_2") (pintype "passive"))
      (node (ref "L6") (pin "1") (pinfunction "1_1") (pintype "passive"))
    )
    (net (code "50") (name "Net-(C15-Pad2)") (class "Default")
      (node (ref "C15") (pin "2") (pinfunction "2_2") (pintype "passive"))
      (node (ref "L7") (pin "2") (pinfunction "2_2") (pintype "passive"))
      (node (ref "L8") (pin "1") (pinfunction "1_1") (pintype "passive"))
    )
    (net (code "51") (name "Net-(C19-Pad2)") (class "Default")
      (node (ref "C19") (pin "2") (pinfunction "2_2") (pintype "passive"))
      (node (ref "L10") (pin "1") (pinfunction "1_1") (pintype "passive"))
      (node (ref "L9") (pin "2") (pinfunction "2_2") (pintype "passive"))
    )
    (net (code "52") (name "Net-(P10-Pad2)") (class "Default")
      (node (ref "P10") (pin "2") (pinfunction "2_2") (pintype "passive"))
      (node (ref "R1") (pin "2") (pinfunction "2_2") (pintype "passive"))
      (node (ref "VR1") (pin "2") (pinfunction "2_2") (pintype "passive"))
      (node (ref "VR1") (pin "3") (pinfunction "3_3") (pintype "passive"))
    )
    (net (code "53") (name "Net-(P11-Pad2)") (class "Default")
      (node (ref "P11") (pin "2") (pinfunction "2_2") (pintype "passive"))
      (node (ref "R2") (pin "2") (pinfunction "2_2") (pintype "passive"))
      (node (ref "VR2") (pin "2") (pinfunction "2_2") (pintype "passive"))
      (node (ref "VR2") (pin "3") (pinfunction "3_3") (pintype "passive"))
    )
    (net (code "54") (name "Net-(P12-Pad2)") (class "Default")
      (node (ref "P12") (pin "2") (pinfunction "2_2") (pintype "passive"))
      (node (ref "R3") (pin "2") (pinfunction "2_2") (pintype "passive"))
      (node (ref "VR3") (pin "2") (pinfunction "2_2") (pintype "passive"))
      (node (ref "VR3") (pin "3") (pinfunction "3_3") (pintype "passive"))
    )
    (net (code "55") (name "Net-(P23-Pad2)") (class "Default")
      (node (ref "P23") (pin "2") (pinfunction "2_2") (pintype "passive"))
      (node (ref "R4") (pin "2") (pinfunction "2_2") (pintype "passive"))
      (node (ref "VR4") (pin "2") (pinfunction "2_2") (pintype "passive"))
      (node (ref "VR4") (pin "3") (pinfunction "3_3") (pintype "passive"))
    )
    (net (code "56") (name "Net-(P24-Pad2)") (class "Default")
      (node (ref "P24") (pin "2") (pinfunction "2_2") (pintype "passive"))
      (node (ref "R5") (pin "2") (pinfunction "2_2") (pintype "passive"))
      (node (ref "VR5") (pin "2") (pinfunction "2_2") (pintype "passive"))
      (node (ref "VR5") (pin "3") (pinfunction "3_3") (pintype "passive"))
    )
    (net (code "57") (name "Net-(P25-Pad2)") (class "Default")
      (node (ref "P25") (pin "2") (pinfunction "2_2") (pintype "passive"))
      (node (ref "R6") (pin "2") (pinfunction "2_2") (pintype "passive"))
      (node (ref "VR6") (pin "2") (pinfunction "2_2") (pintype "passive"))
      (node (ref "VR6") (pin "3") (pinfunction "3_3") (pintype "passive"))
    )
    (net (code "58") (name "Net-(X2-2)") (class "Default")
      (node (ref "P2") (pin "1") (pinfunction "1_1") (pintype "passive"))
      (node (ref "X2") (pin "3") (pinfunction "2_3") (pintype "passive"))
    )
    (net (code "59") (name "Net-(X3-2)") (class "Default")
      (node (ref "P3") (pin "1") (pinfunction "1_1") (pintype "passive"))
      (node (ref "X3") (pin "3") (pinfunction "2_3") (pintype "passive"))
    )
    (net (code "60") (name "Net-(X6-R1_2)") (class "Default")
      (node (ref "X6") (pin "6") (pinfunction "R1_7_6") (pintype "passive"))
      (node (ref "X6") (pin "9") (pinfunction "R1_2_9") (pintype "passive"))
    )
    (net (code "61") (name "Net-(X6-R2_2)") (class "Default")
      (node (ref "X6") (pin "14") (pinfunction "R2_2_14") (pintype "passive"))
      (node (ref "X6") (pin "3") (pinfunction "R2_7_3") (pintype "passive"))
    )
    (net (code "62") (name "Net-(X7-2)") (class "Default")
      (node (ref "P6") (pin "1") (pinfunction "1_1") (pintype "passive"))
      (node (ref "X7") (pin "3") (pinfunction "2_3") (pintype "passive"))
    )
    (net (code "63") (name "Net-(X10-R1_2)") (class "Default")
      (node (ref "X10") (pin "6") (pinfunction "R1_7_6") (pintype "passive"))
      (node (ref "X10") (pin "9") (pinfunction "R1_2_9") (pintype "passive"))
    )
    (net (code "64") (name "Net-(X10-R2_2)") (class "Default")
      (node (ref "X10") (pin "14") (pinfunction "R2_2_14") (pintype "passive"))
      (node (ref "X10") (pin "3") (pinfunction "R2_7_3") (pintype "passive"))
    )
    (net (code "65") (name "Net-(X11-R1_2)") (class "Default")
      (node (ref "X11") (pin "6") (pinfunction "R1_7_6") (pintype "passive"))
      (node (ref "X11") (pin "9") (pinfunction "R1_2_9") (pintype "passive"))
    )
    (net (code "66") (name "Net-(X11-R2_2)") (class "Default")
      (node (ref "X11") (pin "14") (pinfunction "R2_2_14") (pintype "passive"))
      (node (ref "X11") (pin "3") (pinfunction "R2_7_3") (pintype "passive"))
    )
    (net (code "67") (name "Net-(X12-R1_2)") (class "Default")
      (node (ref "X12") (pin "6") (pinfunction "R1_7_6") (pintype "passive"))
      (node (ref "X12") (pin "9") (pinfunction "R1_2_9") (pintype "passive"))
    )
    (net (code "68") (name "Net-(X12-R2_2)") (class "Default")
      (node (ref "X12") (pin "14") (pinfunction "R2_2_14") (pintype "passive"))
      (node (ref "X12") (pin "3") (pinfunction "R2_7_3") (pintype "passive"))
    )
    (net (code "69") (name "VBI") (class "Default")
      (node (ref "P18") (pin "1") (pinfunction "1_1") (pintype "passive"))
      (node (ref "P29") (pin "1") (pinfunction "1_1") (pintype "passive"))
      (node (ref "X11") (pin "2") (pinfunction "R2_6_2") (pintype "passive"))
      (node (ref "X13") (pin "11") (pinfunction "R1_4_11") (pintype "passive"))
    )
    (net (code "70") (name "VCM") (class "Default")
      (node (ref "P26") (pin "1") (pinfunction "1_1") (pintype "passive"))
      (node (ref "P5") (pin "1") (pinfunction "1_1") (pintype "passive"))
      (node (ref "X13") (pin "4") (pinfunction "R1_5_4") (pintype "passive"))
      (node (ref "X6") (pin "5") (pinfunction "R1_6_5") (pintype "passive"))
    )
    (net (code "71") (name "VDD") (class "Default")
      (node (ref "P7") (pin "1") (pinfunction "1_1") (pintype "passive"))
      (node (ref "X10") (pin "2") (pinfunction "R2_6_2") (pintype "passive"))
      (node (ref "X14") (pin "11") (pinfunction "R1_4_11") (pintype "passive"))
      (node (ref "X7") (pin "1") (pinfunction "0_1") (pintype "passive"))
    )
    (net (code "72") (name "VDD3") (class "Default")
      (node (ref "P9") (pin "1") (pinfunction "1_1") (pintype "passive"))
      (node (ref "X10") (pin "5") (pinfunction "R1_6_5") (pintype "passive"))
      (node (ref "X14") (pin "16") (pinfunction "R2_4_16") (pintype "passive"))
      (node (ref "X7") (pin "2") (pinfunction "1_2") (pintype "passive"))
    )
    (net (code "73") (name "VPD") (class "Default")
      (node (ref "P20") (pin "1") (pinfunction "1_1") (pintype "passive"))
      (node (ref "P22") (pin "1") (pinfunction "1_1") (pintype "passive"))
      (node (ref "X11") (pin "5") (pinfunction "R1_6_5") (pintype "passive"))
      (node (ref "X13") (pin "16") (pinfunction "R2_4_16") (pintype "passive"))
    )
    (net (code "74") (name "VR") (class "Default")
      (node (ref "P32") (pin "1") (pinfunction "1_1") (pintype "passive"))
      (node (ref "X12") (pin "5") (pinfunction "R1_6_5") (pintype "passive"))
      (node (ref "X14") (pin "4") (pinfunction "R1_5_4") (pintype "passive"))
      (node (ref "X2") (pin "2") (pinfunction "1_2") (pintype "passive"))
    )
    (net (code "75") (name "VRS") (class "Default")
      (node (ref "P31") (pin "1") (pinfunction "1_1") (pintype "passive"))
      (node (ref "X12") (pin "2") (pinfunction "R2_6_2") (pintype "passive"))
      (node (ref "X14") (pin "1") (pinfunction "R2_5_1") (pintype "passive"))
      (node (ref "X2") (pin "1") (pinfunction "0_1") (pintype "passive"))
    )
    (net (code "76") (name "VRef") (class "Default")
      (node (ref "P13") (pin "2") (pinfunction "2_2") (pintype "passive"))
      (node (ref "P14") (pin "2") (pinfunction "2_2") (pintype "passive"))
      (node (ref "P15") (pin "2") (pinfunction "2_2") (pintype "passive"))
      (node (ref "P16") (pin "2") (pinfunction "2_2") (pintype "passive"))
      (node (ref "P17") (pin "2") (pinfunction "2_2") (pintype "passive"))
      (node (ref "P8") (pin "2") (pinfunction "2_2") (pintype "passive"))
      (node (ref "X3") (pin "2") (pinfunction "1_2") (pintype "passive"))
    )
    (net (code "77") (name "VRef_Relay") (class "Default")
      (node (ref "P21") (pin "1") (pinfunction "1_1") (pintype "passive"))
      (node (ref "X10") (pin "13") (pinfunction "+5_13") (pintype "passive"))
      (node (ref "X11") (pin "13") (pinfunction "+5_13") (pintype "passive"))
      (node (ref "X12") (pin "13") (pinfunction "+5_13") (pintype "passive"))
      (node (ref "X6") (pin "13") (pinfunction "+5_13") (pintype "passive"))
    )
    (net (code "78") (name "VRef_Relay_Shunt") (class "Default")
      (node (ref "P27") (pin "1") (pinfunction "1_1") (pintype "passive"))
      (node (ref "X13") (pin "13") (pinfunction "+5_13") (pintype "passive"))
      (node (ref "X14") (pin "13") (pinfunction "+5_13") (pintype "passive"))
    )
    (net (code "79") (name "VRef_Reserve") (class "Default")
      (node (ref "P28") (pin "1") (pinfunction "X_1") (pintype "passive"))
      (node (ref "P30") (pin "1") (pinfunction "1_1") (pintype "passive"))
    )
    (net (code "80") (name "VTDI") (class "Default")
      (node (ref "P4") (pin "1") (pinfunction "1_1") (pintype "passive"))
      (node (ref "X13") (pin "1") (pinfunction "R2_5_1") (pintype "passive"))
      (node (ref "X3") (pin "1") (pinfunction "0_1") (pintype "passive"))
      (node (ref "X6") (pin "2") (pinfunction "R2_6_2") (pintype "passive"))
    )
    (net (code "81") (name "unconnected-(P19-Y-Pad2)") (class "Default")
      (node (ref "P19") (pin "2") (pinfunction "Y_2") (pintype "passive"))
    )
    (net (code "82") (name "unconnected-(P28-Y-Pad2)") (class "Default")
      (node (ref "P28") (pin "2") (pinfunction "Y_2") (pintype "passive"))
    )
    (net (code "83") (name "unconnected-(X1-+V-Pad3)") (class "Default")
      (node (ref "X1") (pin "3") (pinfunction "+V_3") (pintype "passive"))
    )
    (net (code "84") (name "unconnected-(X4-NC-Pad1)") (class "Default")
      (node (ref "X4") (pin "1") (pinfunction "NC_1") (pintype "passive"))
    )
    (net (code "85") (name "unconnected-(X4-NC-Pad18)") (class "Default")
      (node (ref "X4") (pin "18") (pinfunction "NC_18") (pintype "passive"))
    )
    (net (code "86") (name "unconnected-(X4-NC-Pad19)") (class "Default")
      (node (ref "X4") (pin "19") (pinfunction "NC_19") (pintype "passive"))
    )
    (net (code "87") (name "unconnected-(X4-NC-Pad37)") (class "Default")
      (node (ref "X4") (pin "37") (pinfunction "NC_37") (pintype "passive"))
    )
    (net (code "88") (name "unconnected-(X4-P0.0-Pad15)") (class "Default")
      (node (ref "X4") (pin "15") (pinfunction "P0.0_15") (pintype "passive"))
    )
    (net (code "89") (name "unconnected-(X4-P0.1-Pad33)") (class "Default")
      (node (ref "X4") (pin "33") (pinfunction "P0.1_33") (pintype "passive"))
    )
    (net (code "90") (name "unconnected-(X4-P0.2-Pad14)") (class "Default")
      (node (ref "X4") (pin "14") (pinfunction "P0.2_14") (pintype "passive"))
    )
    (net (code "91") (name "unconnected-(X4-P0.3-Pad32)") (class "Default")
      (node (ref "X4") (pin "32") (pinfunction "P0.3_32") (pintype "passive"))
    )
    (net (code "92") (name "unconnected-(X4-P0.4-Pad13)") (class "Default")
      (node (ref "X4") (pin "13") (pinfunction "P0.4_13") (pintype "passive"))
    )
    (net (code "93") (name "unconnected-(X4-P1.0-Pad10)") (class "Default")
      (node (ref "X4") (pin "10") (pinfunction "P1.0_10") (pintype "passive"))
    )
    (net (code "94") (name "unconnected-(X4-PFI1-Pad36)") (class "Default")
      (node (ref "X4") (pin "36") (pinfunction "PFI1_36") (pintype "passive"))
    )
    (net (code "95") (name "unconnected-(X4-PFI2-Pad17)") (class "Default")
      (node (ref "X4") (pin "17") (pinfunction "PFI2_17") (pintype "passive"))
    )
    (net (code "96") (name "unconnected-(X4-PFI3-Pad35)") (class "Default")
      (node (ref "X4") (pin "35") (pinfunction "PFI3_35") (pintype "passive"))
    )
    (net (code "97") (name "unconnected-(X13-R1_2-Pad9)") (class "Default")
      (node (ref "X13") (pin "9") (pinfunction "R1_2_9") (pintype "passive"))
    )
    (net (code "98") (name "unconnected-(X13-R1_7-Pad6)") (class "Default")
      (node (ref "X13") (pin "6") (pinfunction "R1_7_6") (pintype "passive"))
    )
    (net (code "99") (name "unconnected-(X13-R2_2-Pad14)") (class "Default")
      (node (ref "X13") (pin "14") (pinfunction "R2_2_14") (pintype "passive"))
    )
    (net (code "100") (name "unconnected-(X13-R2_7-Pad3)") (class "Default")
      (node (ref "X13") (pin "3") (pinfunction "R2_7_3") (pintype "passive"))
    )
    (net (code "101") (name "unconnected-(X14-R1_2-Pad9)") (class "Default")
      (node (ref "X14") (pin "9") (pinfunction "R1_2_9") (pintype "passive"))
    )
    (net (code "102") (name "unconnected-(X14-R1_7-Pad6)") (class "Default")
      (node (ref "X14") (pin "6") (pinfunction "R1_7_6") (pintype "passive"))
    )
    (net (code "103") (name "unconnected-(X14-R2_2-Pad14)") (class "Default")
      (node (ref "X14") (pin "14") (pinfunction "R2_2_14") (pintype "passive"))
    )
    (net (code "104") (name "unconnected-(X14-R2_7-Pad3)") (class "Default")
      (node (ref "X14") (pin "3") (pinfunction "R2_7_3") (pintype "passive"))
    )
  )
)
